# XOR_XNOR_1_1.net
KiCad netlist of a schematic drawn in EAGLE
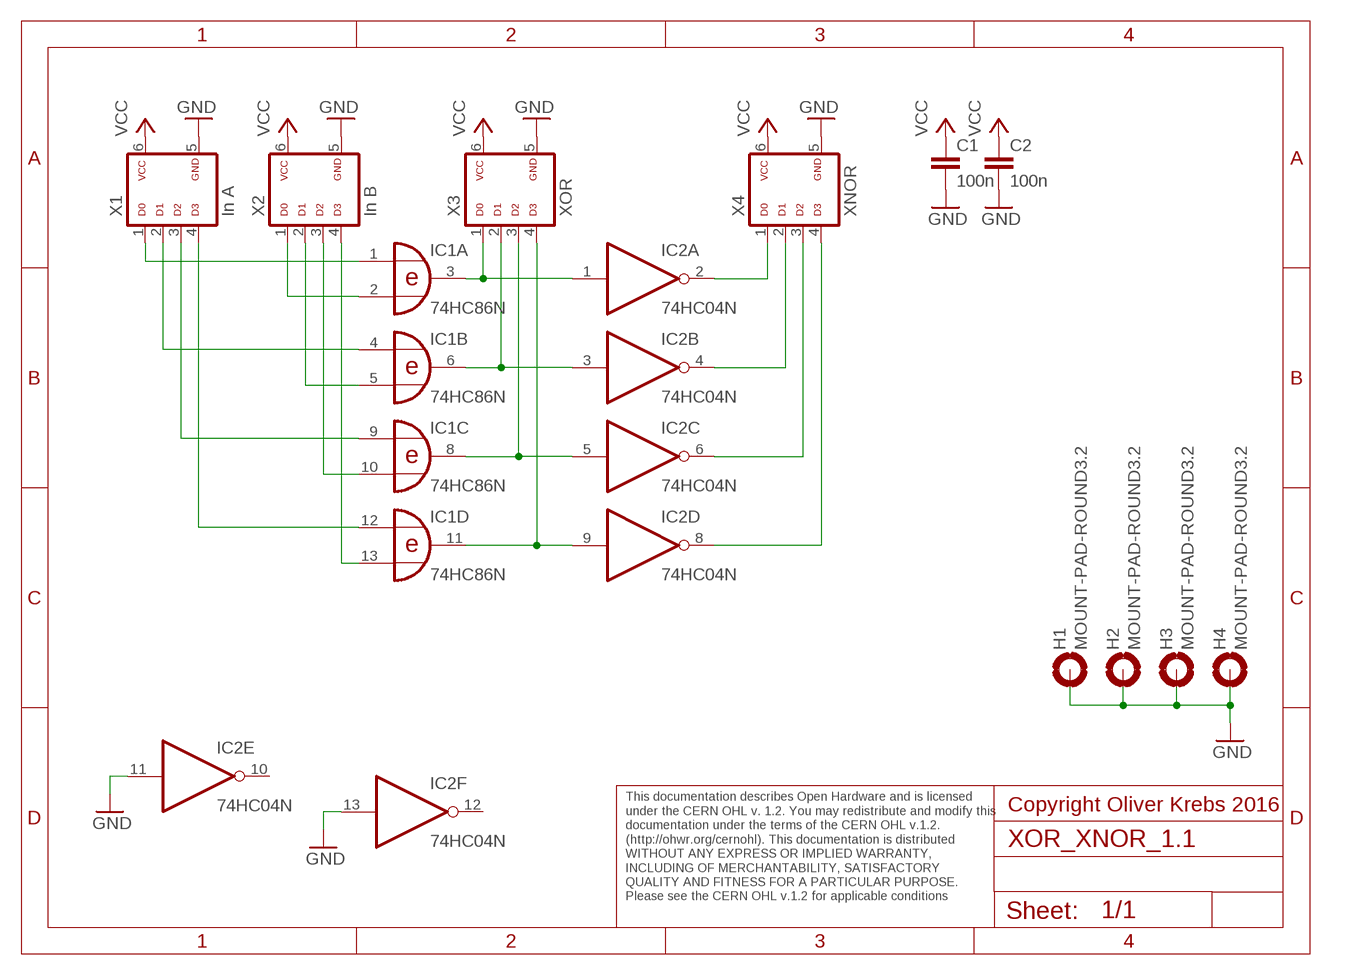
[diagram p0: schematic, sheet 1]

(export (version "E")
  (design (tool "Eeschema 10.0.6"))
  (components
    (comp (ref "C1")
      (value "100n")
      (footprint "eagle-import:C050-025X075")
      (libsource (lib "eagle-import") (part "C-EU050-025X075"))
    )
    (comp (ref "C2")
      (value "100n")
      (footprint "eagle-import:C050-025X075")
      (libsource (lib "eagle-import") (part "C-EU050-025X075"))
    )
    (comp (ref "H1")
      (value "MOUNT-PAD-ROUND3.2")
      (footprint "eagle-import:3,2-PAD")
      (libsource (lib "eagle-import") (part "MOUNT-PAD-ROUND3.2"))
    )
    (comp (ref "H2")
      (value "MOUNT-PAD-ROUND3.2")
      (footprint "eagle-import:3,2-PAD")
      (libsource (lib "eagle-import") (part "MOUNT-PAD-ROUND3.2"))
    )
    (comp (ref "H3")
      (value "MOUNT-PAD-ROUND3.2")
      (footprint "eagle-import:3,2-PAD")
      (libsource (lib "eagle-import") (part "MOUNT-PAD-ROUND3.2"))
    )
    (comp (ref "H4")
      (value "MOUNT-PAD-ROUND3.2")
      (footprint "eagle-import:3,2-PAD")
      (libsource (lib "eagle-import") (part "MOUNT-PAD-ROUND3.2"))
    )
    (comp (ref "IC1")
      (value "74HC86N")
      (footprint "eagle-import:DIL14")
      (libsource (lib "eagle-import") (part "7486NHC"))
    )
    (comp (ref "IC2")
      (value "74HC04N")
      (footprint "eagle-import:DIL14")
      (libsource (lib "eagle-import") (part "7404NHC"))
    )
    (comp (ref "X1")
      (value "In A")
      (footprint "eagle-import:ML-6")
      (libsource (lib "eagle-import") (part "ML6D"))
    )
    (comp (ref "X2")
      (value "In B")
      (footprint "eagle-import:ML-6")
      (libsource (lib "eagle-import") (part "ML6D"))
    )
    (comp (ref "X3")
      (value "XOR")
      (footprint "eagle-import:ML-6")
      (libsource (lib "eagle-import") (part "ML6D"))
    )
    (comp (ref "X4")
      (value "XNOR")
      (footprint "eagle-import:ML-6")
      (libsource (lib "eagle-import") (part "ML6D"))
    )
  )
  (nets
    (net (code "1") (name "GND") (class "Default")
      (node (ref "C1") (pin "2") (pinfunction "2_2") (pintype "passive"))
      (node (ref "C2") (pin "2") (pinfunction "2_2") (pintype "passive"))
      (node (ref "H1") (pin "B3,2") (pinfunction "MOUNT_B3,2") (pintype "passive"))
      (node (ref "H2") (pin "B3,2") (pinfunction "MOUNT_B3,2") (pintype "passive"))
      (node (ref "H3") (pin "B3,2") (pinfunction "MOUNT_B3,2") (pintype "passive"))
      (node (ref "H4") (pin "B3,2") (pinfunction "MOUNT_B3,2") (pintype "passive"))
      (node (ref "IC2") (pin "11") (pinfunction "I_11") (pintype "input"))
      (node (ref "IC2") (pin "13") (pinfunction "I_13") (pintype "input"))
      (node (ref "X1") (pin "5") (pinfunction "5_5") (pintype "passive"))
      (node (ref "X2") (pin "5") (pinfunction "5_5") (pintype "passive"))
      (node (ref "X3") (pin "5") (pinfunction "5_5") (pintype "passive"))
      (node (ref "X4") (pin "5") (pinfunction "5_5") (pintype "passive"))
    )
    (net (code "2") (name "Net-(IC1A-I0)") (class "Default")
      (node (ref "IC1") (pin "1") (pinfunction "I0_1") (pintype "input"))
      (node (ref "X1") (pin "1") (pinfunction "1_1") (pintype "passive"))
    )
    (net (code "3") (name "Net-(IC1A-I1)") (class "Default")
      (node (ref "IC1") (pin "2") (pinfunction "I1_2") (pintype "input"))
      (node (ref "X2") (pin "1") (pinfunction "1_1") (pintype "passive"))
    )
    (net (code "4") (name "Net-(IC1A-O)") (class "Default")
      (node (ref "IC1") (pin "3") (pinfunction "O_3") (pintype "output"))
      (node (ref "IC2") (pin "1") (pinfunction "I_1") (pintype "input"))
      (node (ref "X3") (pin "1") (pinfunction "1_1") (pintype "passive"))
    )
    (net (code "5") (name "Net-(IC1B-I0)") (class "Default")
      (node (ref "IC1") (pin "4") (pinfunction "I0_4") (pintype "input"))
      (node (ref "X1") (pin "2") (pinfunction "2_2") (pintype "passive"))
    )
    (net (code "6") (name "Net-(IC1B-I1)") (class "Default")
      (node (ref "IC1") (pin "5") (pinfunction "I1_5") (pintype "input"))
      (node (ref "X2") (pin "2") (pinfunction "2_2") (pintype "passive"))
    )
    (net (code "7") (name "Net-(IC1B-O)") (class "Default")
      (node (ref "IC1") (pin "6") (pinfunction "O_6") (pintype "output"))
      (node (ref "IC2") (pin "3") (pinfunction "I_3") (pintype "input"))
      (node (ref "X3") (pin "2") (pinfunction "2_2") (pintype "passive"))
    )
    (net (code "8") (name "Net-(IC1C-I0)") (class "Default")
      (node (ref "IC1") (pin "9") (pinfunction "I0_9") (pintype "input"))
      (node (ref "X1") (pin "3") (pinfunction "3_3") (pintype "passive"))
    )
    (net (code "9") (name "Net-(IC1C-I1)") (class "Default")
      (node (ref "IC1") (pin "10") (pinfunction "I1_10") (pintype "input"))
      (node (ref "X2") (pin "3") (pinfunction "3_3") (pintype "passive"))
    )
    (net (code "10") (name "Net-(IC1C-O)") (class "Default")
      (node (ref "IC1") (pin "8") (pinfunction "O_8") (pintype "output"))
      (node (ref "IC2") (pin "5") (pinfunction "I_5") (pintype "input"))
      (node (ref "X3") (pin "3") (pinfunction "3_3") (pintype "passive"))
    )
    (net (code "11") (name "Net-(IC1D-I0)") (class "Default")
      (node (ref "IC1") (pin "12") (pinfunction "I0_12") (pintype "input"))
      (node (ref "X1") (pin "4") (pinfunction "4_4") (pintype "passive"))
    )
    (net (code "12") (name "Net-(IC1D-I1)") (class "Default")
      (node (ref "IC1") (pin "13") (pinfunction "I1_13") (pintype "input"))
      (node (ref "X2") (pin "4") (pinfunction "4_4") (pintype "passive"))
    )
    (net (code "13") (name "Net-(IC1D-O)") (class "Default")
      (node (ref "IC1") (pin "11") (pinfunction "O_11") (pintype "output"))
      (node (ref "IC2") (pin "9") (pinfunction "I_9") (pintype "input"))
      (node (ref "X3") (pin "4") (pinfunction "4_4") (pintype "passive"))
    )
    (net (code "14") (name "Net-(IC2A-O)") (class "Default")
      (node (ref "IC2") (pin "2") (pinfunction "O_2") (pintype "output"))
      (node (ref "X4") (pin "1") (pinfunction "1_1") (pintype "passive"))
    )
    (net (code "15") (name "Net-(IC2B-O)") (class "Default")
      (node (ref "IC2") (pin "4") (pinfunction "O_4") (pintype "output"))
      (node (ref "X4") (pin "2") (pinfunction "2_2") (pintype "passive"))
    )
    (net (code "16") (name "Net-(IC2C-O)") (class "Default")
      (node (ref "IC2") (pin "6") (pinfunction "O_6") (pintype "output"))
      (node (ref "X4") (pin "3") (pinfunction "3_3") (pintype "passive"))
    )
    (net (code "17") (name "Net-(IC2D-O)") (class "Default")
      (node (ref "IC2") (pin "8") (pinfunction "O_8") (pintype "output"))
      (node (ref "X4") (pin "4") (pinfunction "4_4") (pintype "passive"))
    )
    (net (code "18") (name "VCC") (class "Default")
      (node (ref "C1") (pin "1") (pinfunction "1_1") (pintype "passive"))
      (node (ref "C2") (pin "1") (pinfunction "1_1") (pintype "passive"))
      (node (ref "X1") (pin "6") (pinfunction "6_6") (pintype "passive"))
      (node (ref "X2") (pin "6") (pinfunction "6_6") (pintype "passive"))
      (node (ref "X3") (pin "6") (pinfunction "6_6") (pintype "passive"))
      (node (ref "X4") (pin "6") (pinfunction "6_6") (pintype "passive"))
    )
    (net (code "19") (name "unconnected-(IC2E-O-Pad10)") (class "Default")
      (node (ref "IC2") (pin "10") (pinfunction "O_10") (pintype "output"))
    )
    (net (code "20") (name "unconnected-(IC2F-O-Pad12)") (class "Default")
      (node (ref "IC2") (pin "12") (pinfunction "O_12") (pintype "output"))
    )
  )
)
